# mcu.net
KiCad netlist of a schematic drawn in Altium Designer
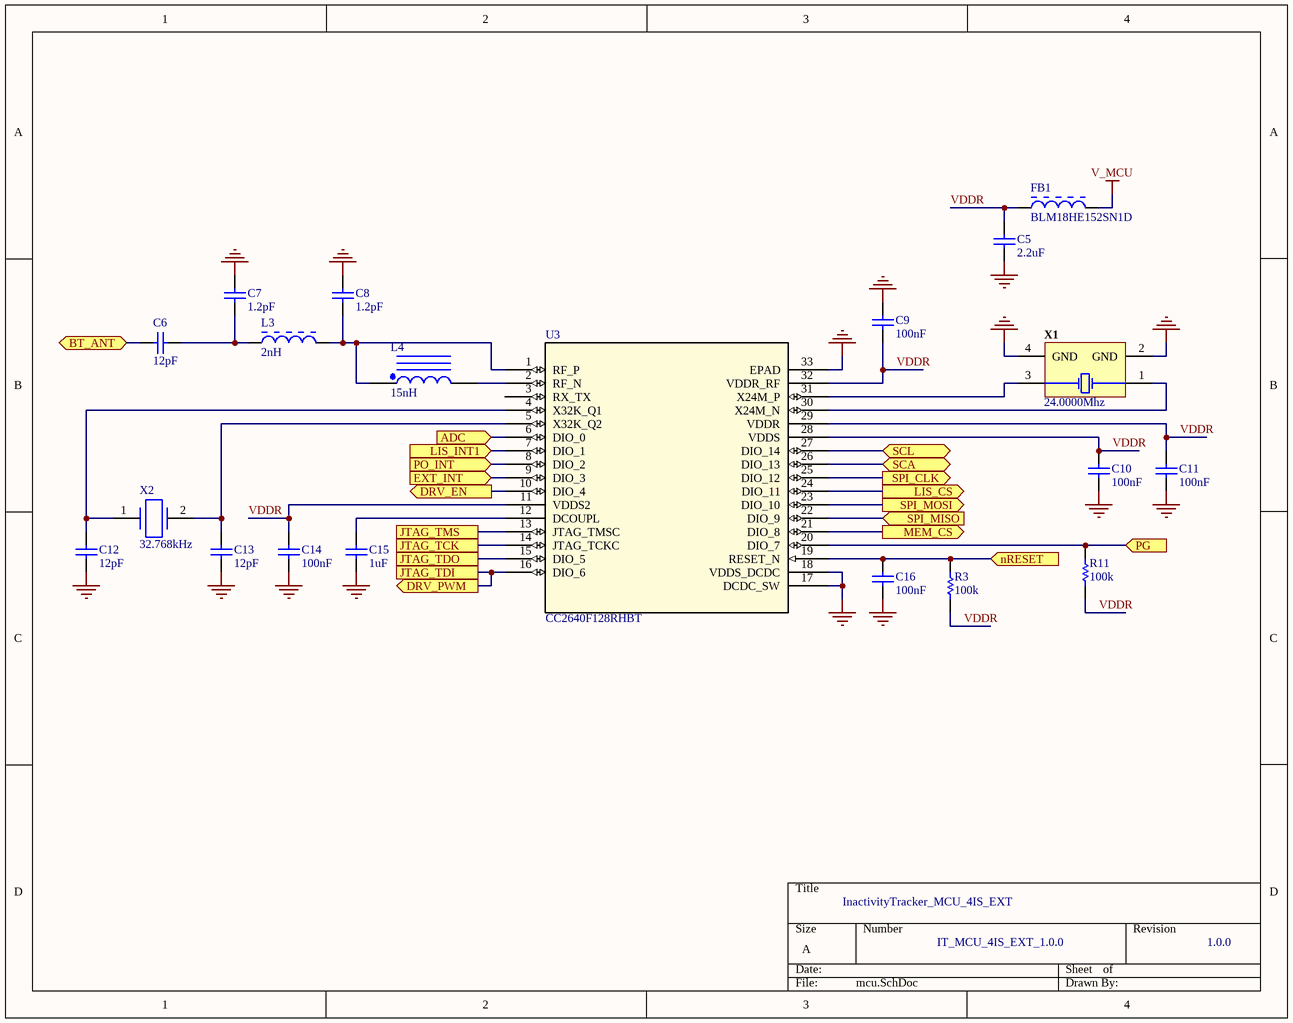
[diagram p0: mcu.SchDoc]

(export (version "E")
  (design (tool "Eeschema 10.0.6"))
  (components
    (comp (ref "C5")
      (value "2.2uF")
      (footprint "CAPC1005X55X25ML05T10")
      (fields (field (name "PART NUMBER") "GRM155R60J225ME15D") (field (name "MANUFACTURER") "Murata"))
      (libsource (lib "Altium Content Vault") (part "CAP"))
    )
    (comp (ref "C6")
      (value "12pF")
      (footprint "CAPC1005X55X25NL05T10")
      (fields (field (name "PART NUMBER") "GRM1555C1H120JA01D") (field (name "MANUFACTURER") "Murata"))
      (libsource (lib "Altium Content Vault") (part "CAP"))
    )
    (comp (ref "C7")
      (value "1.2pF")
      (footprint "CAPC1005X55X25ML05T10")
      (fields (field (name "MANUFACTURER") "Murata") (field (name "PART NUMBER") "GRM1555C1H1R2CA01D"))
      (libsource (lib "Altium Content Vault") (part "CAP"))
    )
    (comp (ref "C8")
      (value "1.2pF")
      (footprint "CAPC1005X55X25ML05T10")
      (fields (field (name "MANUFACTURER") "Murata") (field (name "PART NUMBER") "GRM1555C1H1R2CA01D"))
      (libsource (lib "Altium Content Vault") (part "CAP"))
    )
    (comp (ref "C9")
      (value "100nF")
      (footprint "CAPC1005X55X25NL05T10")
      (fields (field (name "PART NUMBER") "GRM155R71H104KE14D") (field (name "MANUFACTURER") "Murata"))
      (libsource (lib "Altium Content Vault") (part "CAP"))
    )
    (comp (ref "C10")
      (value "100nF")
      (footprint "CAPC1005X55X25NL05T10")
      (fields (field (name "PART NUMBER") "GRM155R71H104KE14D") (field (name "MANUFACTURER") "Murata"))
      (libsource (lib "Altium Content Vault") (part "CAP"))
    )
    (comp (ref "C11")
      (value "100nF")
      (footprint "CAPC1005X55X25NL05T10")
      (fields (field (name "PART NUMBER") "GRM155R71H104KE14D") (field (name "MANUFACTURER") "Murata"))
      (libsource (lib "Altium Content Vault") (part "CAP"))
    )
    (comp (ref "C12")
      (value "12pF")
      (footprint "CAPC1005X55X25NL05T10")
      (fields (field (name "PART NUMBER") "GRM1555C1H120JA01D") (field (name "MANUFACTURER") "Murata"))
      (libsource (lib "Altium Content Vault") (part "CAP"))
    )
    (comp (ref "C13")
      (value "12pF")
      (footprint "CAPC1005X55X25NL05T10")
      (fields (field (name "PART NUMBER") "GRM1555C1H120JA01D") (field (name "MANUFACTURER") "Murata"))
      (libsource (lib "Altium Content Vault") (part "CAP"))
    )
    (comp (ref "C14")
      (value "100nF")
      (footprint "CAPC1005X55X25NL05T10")
      (fields (field (name "PART NUMBER") "GRM155R71H104KE14D") (field (name "MANUFACTURER") "Murata"))
      (libsource (lib "Altium Content Vault") (part "CAP"))
    )
    (comp (ref "C15")
      (value "1uF")
      (footprint "CAPC1005X55X25NL5T10")
      (description "Chip Capacitor, 1 uF, +/- 10%, 6.3 V, -55 to 85 degC, 0402 (1005 Metric), RoHS, Tape and Reel")
      (fields (field (name "TOLERANCE") "10%") (field (name "PARTNUMBER") "GRM155R60J105KE19D"))
      (libsource (lib "Altium Content Vault") (part "CAP-NP-2"))
    )
    (comp (ref "C16")
      (value "100nF")
      (footprint "CAPC1005X55X25NL05T10")
      (fields (field (name "PART NUMBER") "GRM155R71H104KE14D") (field (name "MANUFACTURER") "Murata"))
      (libsource (lib "Altium Content Vault") (part "CAP"))
    )
    (comp (ref "FB1")
      (value "BLM18HE152SN1D")
      (footprint "MURA-BLM18-RF-H4-CHIP-2_V")
      (fields (field (name "MANUFACTURER") "Murata"))
      (libsource (lib "Altium Content Vault") (part "MURA-FB-2"))
    )
    (comp (ref "L3")
      (value "2nH")
      (footprint "MURA-IND0402_V")
      (fields (field (name "MANUFACTURER") "Murata") (field (name "PARTNUMBER") "LQG15HS2N0S02D"))
      (libsource (lib "Altium Content Vault") (part "MURA-INDC-2"))
    )
    (comp (ref "L4")
      (value "15nH")
      (footprint "INDC1005X55X25ML05T10_A")
      (description "Chip Inductor, 15 nH, +/- 5%, 100 MHz, -55 to 125 degC, 0402 (1005 Metric), RoHS, Paper Tape")
      (fields (field (name "TOLERANCE") "5%") (field (name "MANUFACTURER") "Murata"))
      (libsource (lib "Altium Content Vault") (part "IND-DOT-2"))
    )
    (comp (ref "R3")
      (value "100k")
      (footprint "RESC1005X40X25ML05T05")
      (description "Chip Resistor, 100 KOhm, +/- 1%, 0.63 W, -55 to 155 degC, 0402 (1005 Metric), RoHS, Tape and Reel")
      (fields (field (name "TOLERANCE") "1%"))
      (libsource (lib "Altium Content Vault") (part "RES-2"))
    )
    (comp (ref "R11")
      (value "100k")
      (footprint "RESC1005X40X25ML05T05")
      (description "Chip Resistor, 100 KOhm, +/- 1%, 0.63 W, -55 to 155 degC, 0402 (1005 Metric), RoHS, Tape and Reel")
      (fields (field (name "TOLERANCE") "1%"))
      (libsource (lib "Altium Content Vault") (part "RES-2"))
    )
    (comp (ref "U3")
      (value "CC2640F128RHBT")
      (footprint "RHB32_3P45X3P45")
      (description "SimpleLink Wireless MCU")
      (fields (field (name "COPYRIGHT") "Copyright (C) 2018 Accelerated Designs. All rights reserved"))
      (libsource (lib "TIMicrocontrollers") (part "CC2640F128RHBT"))
    )
    (comp (ref "X1")
      (value "24.0000Mhz")
      (footprint "EPSON-TSX-3225_V")
      (description "MHz Range Crystal, 24 MHz, -40 to 85 degC, 4-Pin SMD, RoHS, Tape and Reel")
      (fields (field (name "TOLERANCE") "10PPM") (field (name "MANUFACTURER") "Epson"))
      (libsource (lib "Altium Content Vault") (part "XTAL-1-3-4"))
    )
    (comp (ref "X2")
      (value "32.768kHz")
      (footprint "XTAL320X150X75")
      (description "TXC - 9HT10-32.768KDZY-T - CRYSTAL, 32.768KHZ, 7PF, 3.2 X 1.5MM")
      (fields
        (field (name "MANUFACTURER") "TXC")
        (field (name "MANUFACTURER PART NUMBER") "9HT10-32.768KDZY-T")
      )
      (libsource (lib "InactivityTracker") (part "9HT10-32.768KDZY-T"))
    )
  )
  (nets
    (net (code "1") (name "/ADC") (class "Default")
      (node (ref "U3") (pin "6") (pinfunction "DIO_0_6") (pintype "bidirectional"))
    )
    (net (code "2") (name "/BT_ANT") (class "Default")
      (node (ref "C6") (pin "1") (pinfunction "1_1") (pintype "passive"))
    )
    (net (code "3") (name "/DRV_EN") (class "Default")
      (node (ref "U3") (pin "10") (pinfunction "DIO_4_10") (pintype "bidirectional"))
    )
    (net (code "4") (name "/DRV_PWM") (class "Default")
      (node (ref "U3") (pin "16") (pinfunction "DIO_6_16") (pintype "bidirectional"))
    )
    (net (code "5") (name "/EXT_INT") (class "Default")
      (node (ref "U3") (pin "9") (pinfunction "DIO_3_9") (pintype "bidirectional"))
    )
    (net (code "6") (name "/JTAG_TCK") (class "Default")
      (node (ref "U3") (pin "14") (pinfunction "JTAG_TCKC_14") (pintype "bidirectional"))
    )
    (net (code "7") (name "/JTAG_TDO") (class "Default")
      (node (ref "U3") (pin "15") (pinfunction "DIO_5_15") (pintype "bidirectional"))
    )
    (net (code "8") (name "/JTAG_TMS") (class "Default")
      (node (ref "U3") (pin "13") (pinfunction "JTAG_TMSC_13") (pintype "bidirectional"))
    )
    (net (code "9") (name "/LIS_CS") (class "Default")
      (node (ref "U3") (pin "24") (pinfunction "DIO_11_24") (pintype "bidirectional"))
    )
    (net (code "10") (name "/LIS_INT1") (class "Default")
      (node (ref "U3") (pin "7") (pinfunction "DIO_1_7") (pintype "bidirectional"))
    )
    (net (code "11") (name "/MEM_CS") (class "Default")
      (node (ref "U3") (pin "21") (pinfunction "DIO_8_21") (pintype "bidirectional"))
    )
    (net (code "12") (name "/PG") (class "Default")
      (node (ref "R11") (pin "1") (pinfunction "1_1") (pintype "passive"))
      (node (ref "U3") (pin "20") (pinfunction "DIO_7_20") (pintype "bidirectional"))
    )
    (net (code "13") (name "/PO_INT") (class "Default")
      (node (ref "U3") (pin "8") (pinfunction "DIO_2_8") (pintype "bidirectional"))
    )
    (net (code "14") (name "/SCA") (class "Default")
      (node (ref "U3") (pin "26") (pinfunction "DIO_13_26") (pintype "bidirectional"))
    )
    (net (code "15") (name "/SCL") (class "Default")
      (node (ref "U3") (pin "27") (pinfunction "DIO_14_27") (pintype "bidirectional"))
    )
    (net (code "16") (name "/SPI_CLK") (class "Default")
      (node (ref "U3") (pin "25") (pinfunction "DIO_12_25") (pintype "bidirectional"))
    )
    (net (code "17") (name "/SPI_MISO") (class "Default")
      (node (ref "U3") (pin "22") (pinfunction "DIO_9_22") (pintype "bidirectional"))
    )
    (net (code "18") (name "/SPI_MOSI") (class "Default")
      (node (ref "U3") (pin "23") (pinfunction "DIO_10_23") (pintype "bidirectional"))
    )
    (net (code "19") (name "/VDDR") (class "Default")
      (node (ref "C10") (pin "2") (pinfunction "2_2") (pintype "passive"))
      (node (ref "C11") (pin "2") (pinfunction "2_2") (pintype "passive"))
      (node (ref "C14") (pin "2") (pinfunction "2_2") (pintype "passive"))
      (node (ref "C5") (pin "1") (pinfunction "1_1") (pintype "passive"))
      (node (ref "C9") (pin "1") (pinfunction "1_1") (pintype "passive"))
      (node (ref "FB1") (pin "1") (pinfunction "1_1") (pintype "passive"))
      (node (ref "R11") (pin "2") (pinfunction "2_2") (pintype "passive"))
      (node (ref "R3") (pin "2") (pinfunction "2_2") (pintype "passive"))
      (node (ref "U3") (pin "11") (pinfunction "VDDS2_11") (pintype "power_in"))
      (node (ref "U3") (pin "28") (pinfunction "VDDS_28") (pintype "power_in"))
      (node (ref "U3") (pin "29") (pinfunction "VDDR_29") (pintype "power_in"))
      (node (ref "U3") (pin "32") (pinfunction "VDDR_RF_32") (pintype "power_in"))
    )
    (net (code "20") (name "/nRESET") (class "Default")
      (node (ref "C16") (pin "2") (pinfunction "2_2") (pintype "passive"))
      (node (ref "R3") (pin "1") (pinfunction "1_1") (pintype "passive"))
      (node (ref "U3") (pin "19") (pinfunction "RESET_N_19") (pintype "input"))
    )
    (net (code "21") (name "GND") (class "Default")
      (node (ref "C10") (pin "1") (pinfunction "1_1") (pintype "passive"))
      (node (ref "C11") (pin "1") (pinfunction "1_1") (pintype "passive"))
      (node (ref "C12") (pin "1") (pinfunction "1_1") (pintype "passive"))
      (node (ref "C13") (pin "1") (pinfunction "1_1") (pintype "passive"))
      (node (ref "C14") (pin "1") (pinfunction "1_1") (pintype "passive"))
      (node (ref "C15") (pin "2") (pinfunction "2_2") (pintype "passive"))
      (node (ref "C16") (pin "1") (pinfunction "1_1") (pintype "passive"))
      (node (ref "C5") (pin "2") (pinfunction "2_2") (pintype "passive"))
      (node (ref "C7") (pin "1") (pinfunction "1_1") (pintype "passive"))
      (node (ref "C8") (pin "1") (pinfunction "1_1") (pintype "passive"))
      (node (ref "C9") (pin "2") (pinfunction "2_2") (pintype "passive"))
      (node (ref "U3") (pin "17") (pinfunction "DCDC_SW_17") (pintype "power_in"))
      (node (ref "U3") (pin "18") (pinfunction "VDDS_DCDC_18") (pintype "power_in"))
      (node (ref "U3") (pin "33") (pinfunction "EPAD_33") (pintype "passive"))
      (node (ref "X1") (pin "2") (pinfunction "GND_2") (pintype "power_in"))
      (node (ref "X1") (pin "4") (pinfunction "GND_4") (pintype "power_in"))
    )
    (net (code "22") (name "Net-(C6-Pad2)") (class "Default")
      (node (ref "C6") (pin "2") (pinfunction "2_2") (pintype "passive"))
      (node (ref "C7") (pin "2") (pinfunction "2_2") (pintype "passive"))
      (node (ref "L3") (pin "1") (pinfunction "1_1") (pintype "passive"))
    )
    (net (code "23") (name "Net-(U3-DCOUPL)") (class "Default")
      (node (ref "C15") (pin "1") (pinfunction "1_1") (pintype "passive"))
      (node (ref "U3") (pin "12") (pinfunction "DCOUPL_12") (pintype "power_in"))
    )
    (net (code "24") (name "Net-(U3-RF_N)") (class "Default")
      (node (ref "L4") (pin "2") (pinfunction "2_2") (pintype "passive"))
      (node (ref "U3") (pin "2") (pinfunction "RF_N_2") (pintype "bidirectional"))
    )
    (net (code "25") (name "Net-(U3-RF_P)") (class "Default")
      (node (ref "C8") (pin "2") (pinfunction "2_2") (pintype "passive"))
      (node (ref "L3") (pin "2") (pinfunction "2_2") (pintype "passive"))
      (node (ref "L4") (pin "1") (pinfunction "1_1") (pintype "passive"))
      (node (ref "U3") (pin "1") (pinfunction "RF_P_1") (pintype "bidirectional"))
    )
    (net (code "26") (name "Net-(U3-X24M_N)") (class "Default")
      (node (ref "U3") (pin "30") (pinfunction "X24M_N_30") (pintype "bidirectional"))
      (node (ref "X1") (pin "1") (pinfunction "X1_1") (pintype "passive"))
    )
    (net (code "27") (name "Net-(U3-X24M_P)") (class "Default")
      (node (ref "U3") (pin "31") (pinfunction "X24M_P_31") (pintype "bidirectional"))
      (node (ref "X1") (pin "3") (pinfunction "X2_3") (pintype "passive"))
    )
    (net (code "28") (name "Net-(U3-X32K_Q1)") (class "Default")
      (node (ref "C12") (pin "2") (pinfunction "2_2") (pintype "passive"))
      (node (ref "U3") (pin "4") (pinfunction "X32K_Q1_4") (pintype "bidirectional"))
      (node (ref "X2") (pin "1") (pinfunction "1_1") (pintype "passive"))
    )
    (net (code "29") (name "Net-(U3-X32K_Q2)") (class "Default")
      (node (ref "C13") (pin "2") (pinfunction "2_2") (pintype "passive"))
      (node (ref "U3") (pin "5") (pinfunction "X32K_Q2_5") (pintype "bidirectional"))
      (node (ref "X2") (pin "2") (pinfunction "2_2") (pintype "passive"))
    )
    (net (code "30") (name "V_MCU") (class "Default")
      (node (ref "FB1") (pin "2") (pinfunction "2_2") (pintype "passive"))
    )
    (net (code "31") (name "unconnected-(U3-RX_TX-Pad3)") (class "Default")
      (node (ref "U3") (pin "3") (pinfunction "RX_TX_3") (pintype "bidirectional"))
    )
  )
)
